# BaseCircuit_DT.net
KiCad netlist of a schematic drawn in Altium Designer
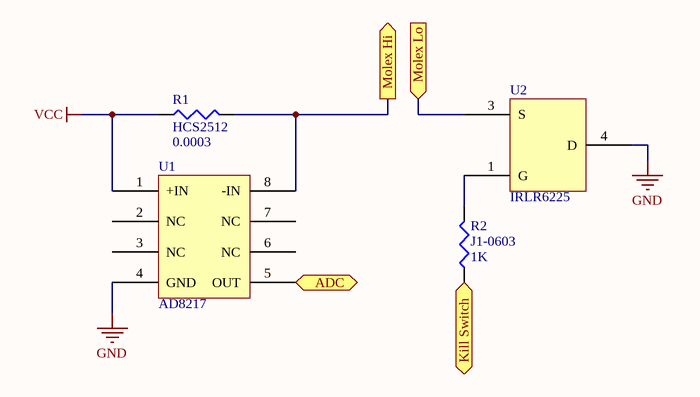
[diagram p0: BaseCircuit_DT.SchDoc]

(export (version "E")
  (design (tool "Eeschema 10.0.6"))
  (components
    (comp (ref "R1")
      (value "HCS2512")
      (footprint "HCS2512FTL300CT-ND_DT")
      (description "Resistor")
      (fields (field (name "ALTIUM_VALUE") "0.0003") (field (name "PUBLISHER") "Altium Limited"))
      (libsource (lib "Miscellaneous Devices") (part "Res3"))
    )
    (comp (ref "R2")
      (value "J1-0603")
      (footprint "J1-0603")
      (description "Resistor")
      (fields (field (name "ALTIUM_VALUE") "1K") (field (name "PUBLISHER") "Altium Limited"))
      (libsource (lib "Miscellaneous Devices") (part "Res3"))
    )
    (comp (ref "U1")
      (value "AD8217")
      (footprint "AD8217_DT:AD8217_DT")
      (libsource (lib "AD8217_DT") (part "Component_1"))
    )
    (comp (ref "U2")
      (value "IRLR6225")
      (footprint "IRLR6225_DT")
      (libsource (lib "IRLR6225_DT") (part "Component_1"))
    )
  )
  (nets
    (net (code "1") (name "/ADC") (class "Default")
      (node (ref "U1") (pin "5") (pinfunction "OUT_5") (pintype "passive"))
    )
    (net (code "2") (name "/Kill Switch") (class "Default")
      (node (ref "R2") (pin "1") (pinfunction "1_1") (pintype "passive"))
    )
    (net (code "3") (name "/Molex Hi") (class "Default")
      (node (ref "R1") (pin "2") (pinfunction "2_2") (pintype "passive"))
      (node (ref "U1") (pin "8") (pinfunction "-IN_8") (pintype "passive"))
    )
    (net (code "4") (name "/Molex Lo") (class "Default")
      (node (ref "U2") (pin "3") (pinfunction "S_3") (pintype "passive"))
    )
    (net (code "5") (name "GND") (class "Default")
      (node (ref "U1") (pin "4") (pinfunction "GND_4") (pintype "passive"))
      (node (ref "U2") (pin "4") (pinfunction "D_4") (pintype "passive"))
    )
    (net (code "6") (name "Net-(U2-G)") (class "Default")
      (node (ref "R2") (pin "2") (pinfunction "2_2") (pintype "passive"))
      (node (ref "U2") (pin "1") (pinfunction "G_1") (pintype "passive"))
    )
    (net (code "7") (name "VCC") (class "Default")
      (node (ref "R1") (pin "1") (pinfunction "1_1") (pintype "passive"))
      (node (ref "U1") (pin "1") (pinfunction "+IN_1") (pintype "passive"))
    )
    (net (code "8") (name "unconnected-(U1-NC-Pad2)") (class "Default")
      (node (ref "U1") (pin "2") (pinfunction "NC_2") (pintype "passive"))
    )
    (net (code "9") (name "unconnected-(U1-NC-Pad3)") (class "Default")
      (node (ref "U1") (pin "3") (pinfunction "NC_3") (pintype "passive"))
    )
    (net (code "10") (name "unconnected-(U1-NC-Pad6)") (class "Default")
      (node (ref "U1") (pin "6") (pinfunction "NC_6") (pintype "passive"))
    )
    (net (code "11") (name "unconnected-(U1-NC-Pad7)") (class "Default")
      (node (ref "U1") (pin "7") (pinfunction "NC_7") (pintype "passive"))
    )
  )
)
